# Connectors.net
KiCad netlist of a schematic drawn in Altium Designer
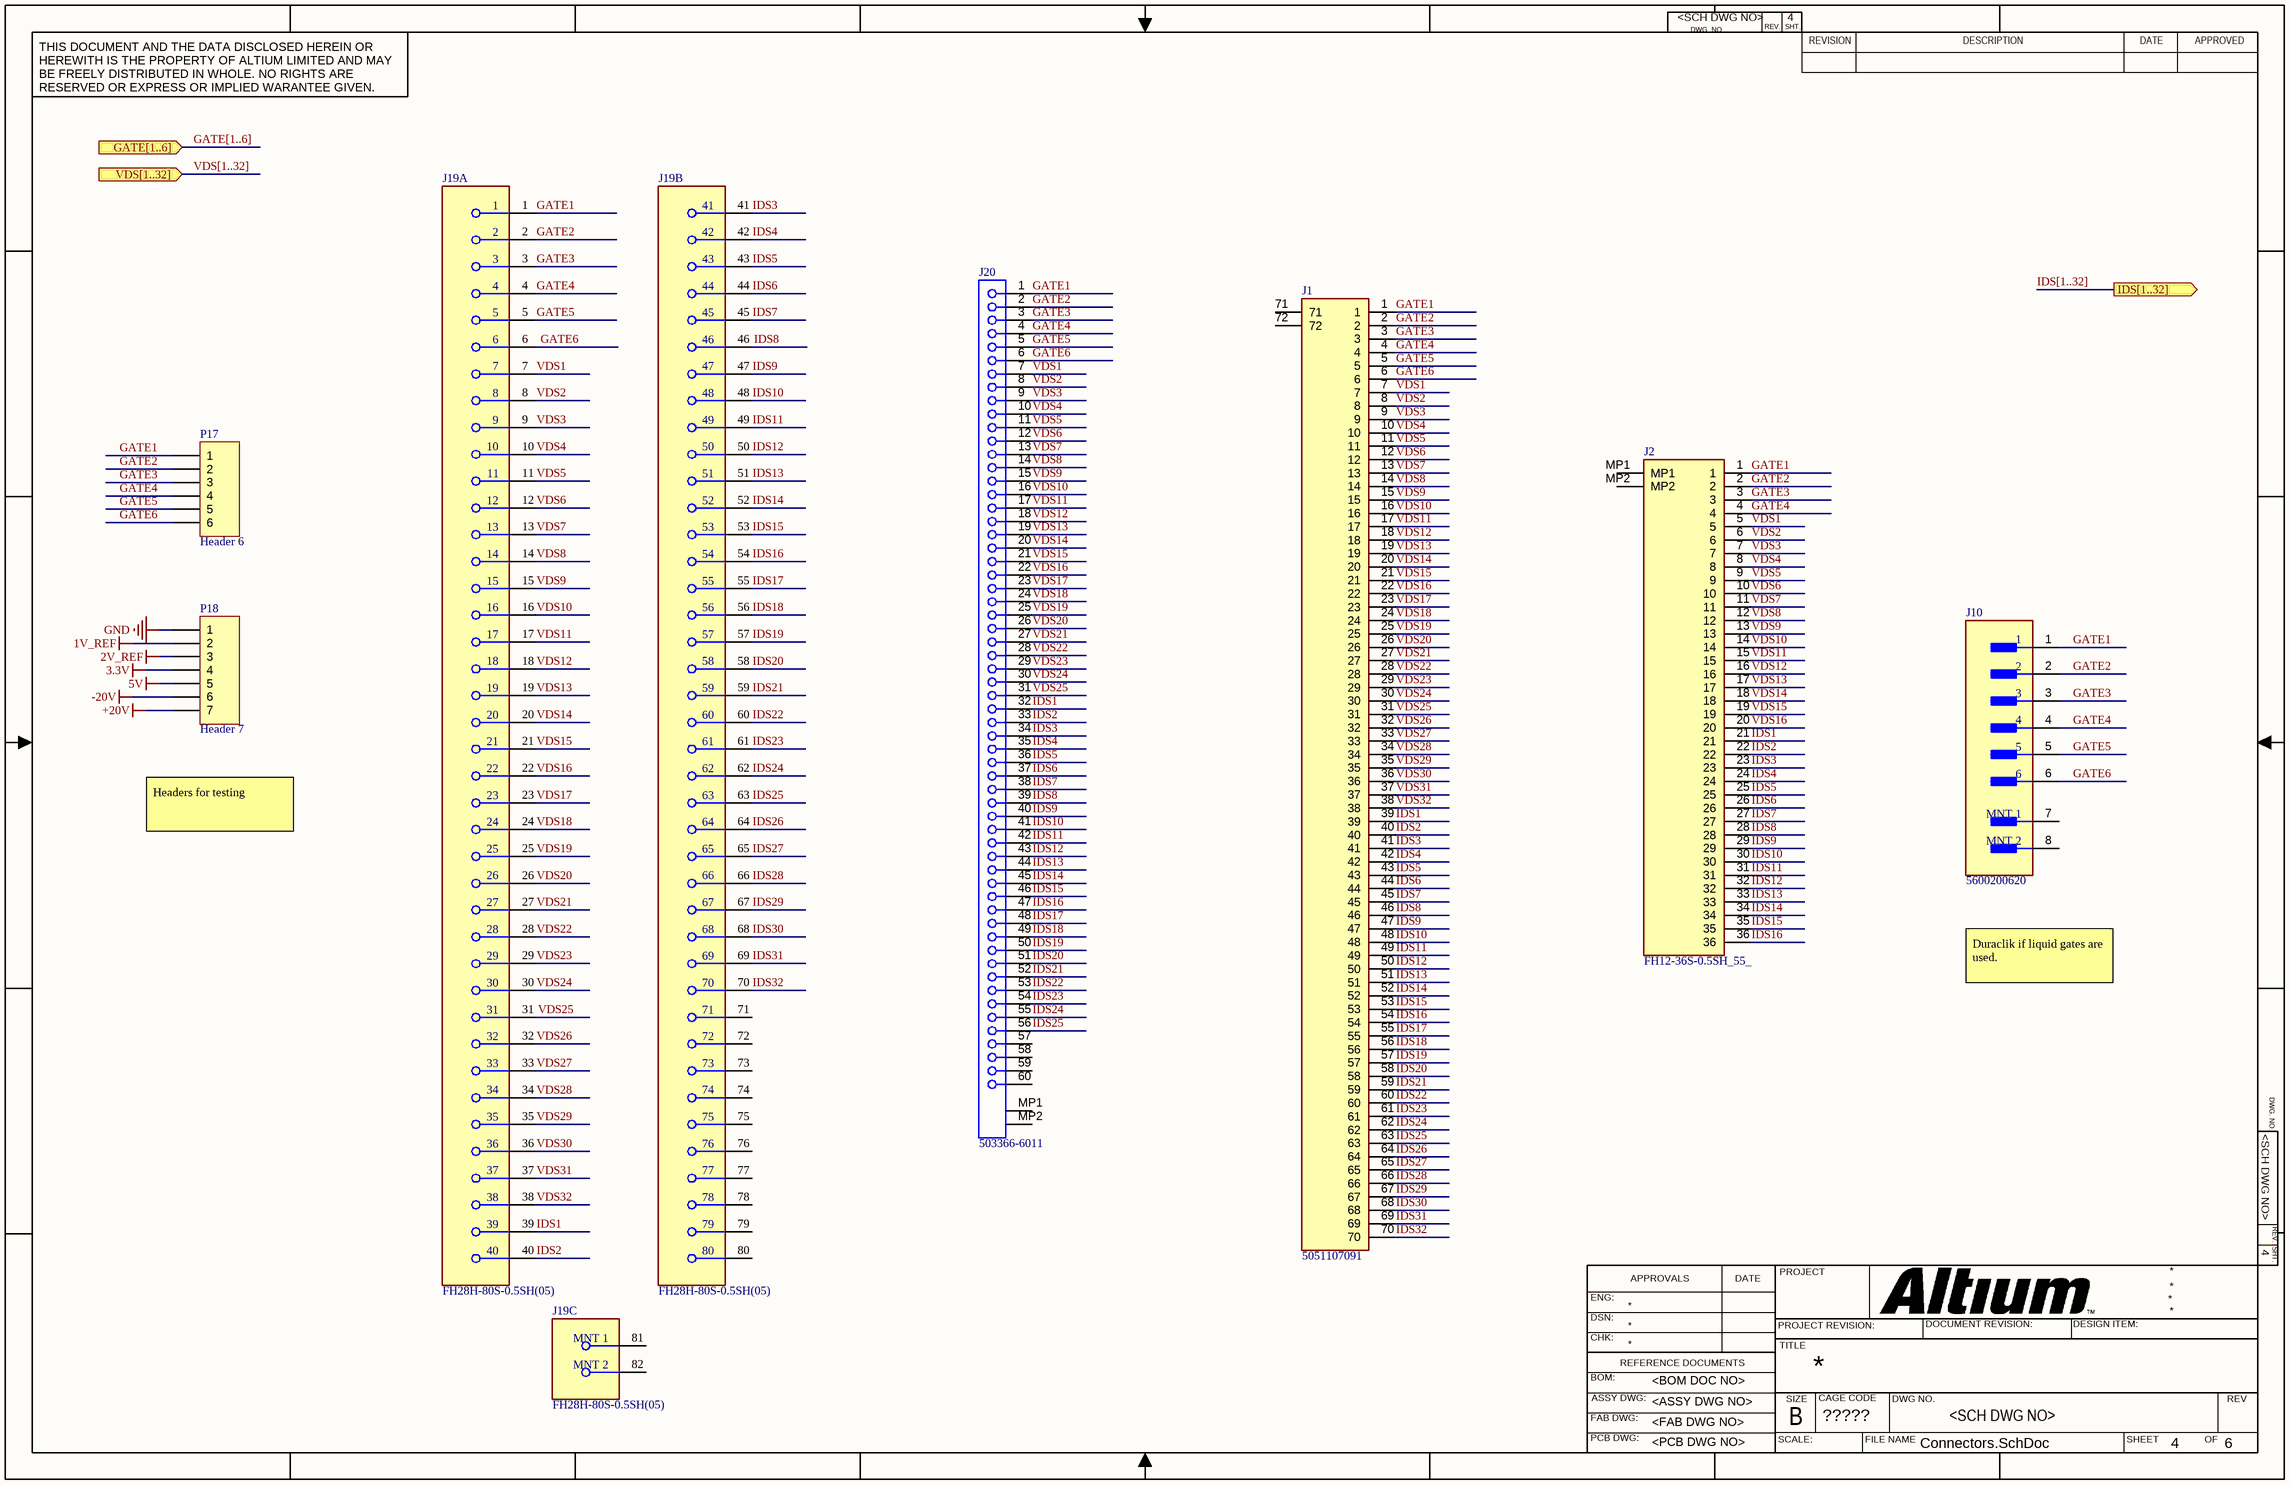
[diagram p0: Connectors.SchDoc]

(export (version "E")
  (design (tool "Eeschema 10.0.6"))
  (components
    (comp (ref "J1")
      (value "5051107091")
      (footprint "5051107091")
      (description "Connector")
      (libsource (lib "SamacSys") (part "5051107091"))
    )
    (comp (ref "J2")
      (value "FH12-36S-0.5SH_55_")
      (footprint "FH1236S05SH55")
      (description "Connector")
      (fields
        (field (name "MANUFACTURER_PART_NUMBER") "FH12-36S-0.5SH(55)")
        (field (name "MOUSER PART NUMBER") "798-FH12-36S-0.5SH55")
      )
      (libsource (lib "SamacSys") (part "FH12-36S-0.5SH_55_"))
    )
    (comp (ref "J10")
      (value "5600200620")
      (footprint "FP-5600200620-MFG")
      (description "CONN HEADER SMD 6POS 2MM")
      (fields
        (field (name "OCTOPART") "https://octopart.com/5600200620-molex-51767481")
        (field (name "MANUFACTURER") "Molex")
      )
      (libsource (lib "Altium Content Vault") (part "ed24c53d9ba001d1a2a686240a95171"))
    )
    (comp (ref "J19")
      (value "FH28H-80S-0.5SH(05)")
      (footprint "FP-FH28H-80S-0_5SH_05-MFG")
      (description "CONN FFC BOTTOM 80POS 0.50MM R/A")
      (libsource (lib "Altium Content Vault") (part "08075b3669470a400ec152efcfe4938"))
    )
    (comp (ref "J20")
      (value "503366-6011")
      (footprint "MOLX-503366-6011")
      (fields (field (name "MANUFACTURER") "Molex"))
      (libsource (lib "Altium Content Vault") (part "MOLX-503366-6011"))
    )
    (comp (ref "P17")
      (value "Header 6")
      (footprint "HDR1X6")
      (description "Header, 6-Pin")
      (fields (field (name "PUBLISHER") "Altium Limited"))
      (libsource (lib "Miscellaneous Connectors") (part "Header 6"))
    )
    (comp (ref "P18")
      (value "Header 7")
      (footprint "HDR1X7")
      (description "Header, 7-Pin")
      (fields (field (name "PUBLISHER") "Altium Limited"))
      (libsource (lib "Miscellaneous Connectors") (part "Header 7"))
    )
  )
  (nets
    (net (code "1") (name "+20V") (class "Default")
      (node (ref "P18") (pin "7") (pinfunction "7_7") (pintype "passive"))
    )
    (net (code "2") (name "-20V") (class "Default")
      (node (ref "P18") (pin "6") (pinfunction "6_6") (pintype "passive"))
    )
    (net (code "3") (name "/GATE1") (class "Default")
      (node (ref "J1") (pin "1") (pinfunction "1_1") (pintype "passive"))
      (node (ref "J10") (pin "1") (pinfunction "1_1") (pintype "passive"))
      (node (ref "J19") (pin "1") (pinfunction "1_1") (pintype "passive"))
      (node (ref "J2") (pin "1") (pinfunction "1_1") (pintype "passive"))
      (node (ref "J20") (pin "1") (pinfunction "1_1") (pintype "passive"))
      (node (ref "P17") (pin "1") (pinfunction "1_1") (pintype "passive"))
    )
    (net (code "4") (name "/GATE2") (class "Default")
      (node (ref "J1") (pin "2") (pinfunction "2_2") (pintype "passive"))
      (node (ref "J10") (pin "2") (pinfunction "2_2") (pintype "passive"))
      (node (ref "J19") (pin "2") (pinfunction "2_2") (pintype "passive"))
      (node (ref "J2") (pin "2") (pinfunction "2_2") (pintype "passive"))
      (node (ref "J20") (pin "2") (pinfunction "2_2") (pintype "passive"))
      (node (ref "P17") (pin "2") (pinfunction "2_2") (pintype "passive"))
    )
    (net (code "5") (name "/GATE3") (class "Default")
      (node (ref "J1") (pin "3") (pinfunction "3_3") (pintype "passive"))
      (node (ref "J10") (pin "3") (pinfunction "3_3") (pintype "passive"))
      (node (ref "J19") (pin "3") (pinfunction "3_3") (pintype "passive"))
      (node (ref "J2") (pin "3") (pinfunction "3_3") (pintype "passive"))
      (node (ref "J20") (pin "3") (pinfunction "3_3") (pintype "passive"))
      (node (ref "P17") (pin "3") (pinfunction "3_3") (pintype "passive"))
    )
    (net (code "6") (name "/GATE4") (class "Default")
      (node (ref "J1") (pin "4") (pinfunction "4_4") (pintype "passive"))
      (node (ref "J10") (pin "4") (pinfunction "4_4") (pintype "passive"))
      (node (ref "J19") (pin "4") (pinfunction "4_4") (pintype "passive"))
      (node (ref "J2") (pin "4") (pinfunction "4_4") (pintype "passive"))
      (node (ref "J20") (pin "4") (pinfunction "4_4") (pintype "passive"))
      (node (ref "P17") (pin "4") (pinfunction "4_4") (pintype "passive"))
    )
    (net (code "7") (name "/GATE5") (class "Default")
      (node (ref "J1") (pin "5") (pinfunction "5_5") (pintype "passive"))
      (node (ref "J10") (pin "5") (pinfunction "5_5") (pintype "passive"))
      (node (ref "J19") (pin "5") (pinfunction "5_5") (pintype "passive"))
      (node (ref "J20") (pin "5") (pinfunction "5_5") (pintype "passive"))
      (node (ref "P17") (pin "5") (pinfunction "5_5") (pintype "passive"))
    )
    (net (code "8") (name "/GATE6") (class "Default")
      (node (ref "J1") (pin "6") (pinfunction "6_6") (pintype "passive"))
      (node (ref "J10") (pin "6") (pinfunction "6_6") (pintype "passive"))
      (node (ref "J19") (pin "6") (pinfunction "6_6") (pintype "passive"))
      (node (ref "J20") (pin "6") (pinfunction "6_6") (pintype "passive"))
      (node (ref "P17") (pin "6") (pinfunction "6_6") (pintype "passive"))
    )
    (net (code "10") (name "/IDS1") (class "Default")
      (node (ref "J1") (pin "39") (pinfunction "39_39") (pintype "passive"))
      (node (ref "J19") (pin "39") (pinfunction "39_39") (pintype "passive"))
      (node (ref "J2") (pin "21") (pinfunction "21_21") (pintype "passive"))
      (node (ref "J20") (pin "32") (pinfunction "32_32") (pintype "passive"))
    )
    (net (code "11") (name "/IDS2") (class "Default")
      (node (ref "J1") (pin "40") (pinfunction "40_40") (pintype "passive"))
      (node (ref "J19") (pin "40") (pinfunction "40_40") (pintype "passive"))
      (node (ref "J2") (pin "22") (pinfunction "22_22") (pintype "passive"))
      (node (ref "J20") (pin "33") (pinfunction "33_33") (pintype "passive"))
    )
    (net (code "12") (name "/IDS3") (class "Default")
      (node (ref "J1") (pin "41") (pinfunction "41_41") (pintype "passive"))
      (node (ref "J19") (pin "41") (pinfunction "41_41") (pintype "passive"))
      (node (ref "J2") (pin "23") (pinfunction "23_23") (pintype "passive"))
      (node (ref "J20") (pin "34") (pinfunction "34_34") (pintype "passive"))
    )
    (net (code "13") (name "/IDS4") (class "Default")
      (node (ref "J1") (pin "42") (pinfunction "42_42") (pintype "passive"))
      (node (ref "J19") (pin "42") (pinfunction "42_42") (pintype "passive"))
      (node (ref "J2") (pin "24") (pinfunction "24_24") (pintype "passive"))
      (node (ref "J20") (pin "35") (pinfunction "35_35") (pintype "passive"))
    )
    (net (code "14") (name "/IDS5") (class "Default")
      (node (ref "J1") (pin "43") (pinfunction "43_43") (pintype "passive"))
      (node (ref "J19") (pin "43") (pinfunction "43_43") (pintype "passive"))
      (node (ref "J2") (pin "25") (pinfunction "25_25") (pintype "passive"))
      (node (ref "J20") (pin "36") (pinfunction "36_36") (pintype "passive"))
    )
    (net (code "15") (name "/IDS6") (class "Default")
      (node (ref "J1") (pin "44") (pinfunction "44_44") (pintype "passive"))
      (node (ref "J19") (pin "44") (pinfunction "44_44") (pintype "passive"))
      (node (ref "J2") (pin "26") (pinfunction "26_26") (pintype "passive"))
      (node (ref "J20") (pin "37") (pinfunction "37_37") (pintype "passive"))
    )
    (net (code "16") (name "/IDS7") (class "Default")
      (node (ref "J1") (pin "45") (pinfunction "45_45") (pintype "passive"))
      (node (ref "J19") (pin "45") (pinfunction "45_45") (pintype "passive"))
      (node (ref "J2") (pin "27") (pinfunction "27_27") (pintype "passive"))
      (node (ref "J20") (pin "38") (pinfunction "38_38") (pintype "passive"))
    )
    (net (code "17") (name "/IDS8") (class "Default")
      (node (ref "J1") (pin "46") (pinfunction "46_46") (pintype "passive"))
      (node (ref "J19") (pin "46") (pinfunction "46_46") (pintype "passive"))
      (node (ref "J2") (pin "28") (pinfunction "28_28") (pintype "passive"))
      (node (ref "J20") (pin "39") (pinfunction "39_39") (pintype "passive"))
    )
    (net (code "18") (name "/IDS9") (class "Default")
      (node (ref "J1") (pin "47") (pinfunction "47_47") (pintype "passive"))
      (node (ref "J19") (pin "47") (pinfunction "47_47") (pintype "passive"))
      (node (ref "J2") (pin "29") (pinfunction "29_29") (pintype "passive"))
      (node (ref "J20") (pin "40") (pinfunction "40_40") (pintype "passive"))
    )
    (net (code "19") (name "/IDS10") (class "Default")
      (node (ref "J1") (pin "48") (pinfunction "48_48") (pintype "passive"))
      (node (ref "J19") (pin "48") (pinfunction "48_48") (pintype "passive"))
      (node (ref "J2") (pin "30") (pinfunction "30_30") (pintype "passive"))
      (node (ref "J20") (pin "41") (pinfunction "41_41") (pintype "passive"))
    )
    (net (code "20") (name "/IDS11") (class "Default")
      (node (ref "J1") (pin "49") (pinfunction "49_49") (pintype "passive"))
      (node (ref "J19") (pin "49") (pinfunction "49_49") (pintype "passive"))
      (node (ref "J2") (pin "31") (pinfunction "31_31") (pintype "passive"))
      (node (ref "J20") (pin "42") (pinfunction "42_42") (pintype "passive"))
    )
    (net (code "21") (name "/IDS12") (class "Default")
      (node (ref "J1") (pin "50") (pinfunction "50_50") (pintype "passive"))
      (node (ref "J19") (pin "50") (pinfunction "50_50") (pintype "passive"))
      (node (ref "J2") (pin "32") (pinfunction "32_32") (pintype "passive"))
      (node (ref "J20") (pin "43") (pinfunction "43_43") (pintype "passive"))
    )
    (net (code "22") (name "/IDS13") (class "Default")
      (node (ref "J1") (pin "51") (pinfunction "51_51") (pintype "passive"))
      (node (ref "J19") (pin "51") (pinfunction "51_51") (pintype "passive"))
      (node (ref "J2") (pin "33") (pinfunction "33_33") (pintype "passive"))
      (node (ref "J20") (pin "44") (pinfunction "44_44") (pintype "passive"))
    )
    (net (code "23") (name "/IDS14") (class "Default")
      (node (ref "J1") (pin "52") (pinfunction "52_52") (pintype "passive"))
      (node (ref "J19") (pin "52") (pinfunction "52_52") (pintype "passive"))
      (node (ref "J2") (pin "34") (pinfunction "34_34") (pintype "passive"))
      (node (ref "J20") (pin "45") (pinfunction "45_45") (pintype "passive"))
    )
    (net (code "24") (name "/IDS15") (class "Default")
      (node (ref "J1") (pin "53") (pinfunction "53_53") (pintype "passive"))
      (node (ref "J19") (pin "53") (pinfunction "53_53") (pintype "passive"))
      (node (ref "J2") (pin "35") (pinfunction "35_35") (pintype "passive"))
      (node (ref "J20") (pin "46") (pinfunction "46_46") (pintype "passive"))
    )
    (net (code "25") (name "/IDS16") (class "Default")
      (node (ref "J1") (pin "54") (pinfunction "54_54") (pintype "passive"))
      (node (ref "J19") (pin "54") (pinfunction "54_54") (pintype "passive"))
      (node (ref "J2") (pin "36") (pinfunction "36_36") (pintype "passive"))
      (node (ref "J20") (pin "47") (pinfunction "47_47") (pintype "passive"))
    )
    (net (code "26") (name "/IDS17") (class "Default")
      (node (ref "J1") (pin "55") (pinfunction "55_55") (pintype "passive"))
      (node (ref "J19") (pin "55") (pinfunction "55_55") (pintype "passive"))
      (node (ref "J20") (pin "48") (pinfunction "48_48") (pintype "passive"))
    )
    (net (code "27") (name "/IDS18") (class "Default")
      (node (ref "J1") (pin "56") (pinfunction "56_56") (pintype "passive"))
      (node (ref "J19") (pin "56") (pinfunction "56_56") (pintype "passive"))
      (node (ref "J20") (pin "49") (pinfunction "49_49") (pintype "passive"))
    )
    (net (code "28") (name "/IDS19") (class "Default")
      (node (ref "J1") (pin "57") (pinfunction "57_57") (pintype "passive"))
      (node (ref "J19") (pin "57") (pinfunction "57_57") (pintype "passive"))
      (node (ref "J20") (pin "50") (pinfunction "50_50") (pintype "passive"))
    )
    (net (code "29") (name "/IDS20") (class "Default")
      (node (ref "J1") (pin "58") (pinfunction "58_58") (pintype "passive"))
      (node (ref "J19") (pin "58") (pinfunction "58_58") (pintype "passive"))
      (node (ref "J20") (pin "51") (pinfunction "51_51") (pintype "passive"))
    )
    (net (code "30") (name "/IDS21") (class "Default")
      (node (ref "J1") (pin "59") (pinfunction "59_59") (pintype "passive"))
      (node (ref "J19") (pin "59") (pinfunction "59_59") (pintype "passive"))
      (node (ref "J20") (pin "52") (pinfunction "52_52") (pintype "passive"))
    )
    (net (code "31") (name "/IDS22") (class "Default")
      (node (ref "J1") (pin "60") (pinfunction "60_60") (pintype "passive"))
      (node (ref "J19") (pin "60") (pinfunction "60_60") (pintype "passive"))
      (node (ref "J20") (pin "53") (pinfunction "53_53") (pintype "passive"))
    )
    (net (code "32") (name "/IDS23") (class "Default")
      (node (ref "J1") (pin "61") (pinfunction "61_61") (pintype "passive"))
      (node (ref "J19") (pin "61") (pinfunction "61_61") (pintype "passive"))
      (node (ref "J20") (pin "54") (pinfunction "54_54") (pintype "passive"))
    )
    (net (code "33") (name "/IDS24") (class "Default")
      (node (ref "J1") (pin "62") (pinfunction "62_62") (pintype "passive"))
      (node (ref "J19") (pin "62") (pinfunction "62_62") (pintype "passive"))
      (node (ref "J20") (pin "55") (pinfunction "55_55") (pintype "passive"))
    )
    (net (code "34") (name "/IDS25") (class "Default")
      (node (ref "J1") (pin "63") (pinfunction "63_63") (pintype "passive"))
      (node (ref "J19") (pin "63") (pinfunction "63_63") (pintype "passive"))
      (node (ref "J20") (pin "56") (pinfunction "56_56") (pintype "passive"))
    )
    (net (code "35") (name "/IDS26") (class "Default")
      (node (ref "J1") (pin "64") (pinfunction "64_64") (pintype "passive"))
      (node (ref "J19") (pin "64") (pinfunction "64_64") (pintype "passive"))
    )
    (net (code "36") (name "/IDS27") (class "Default")
      (node (ref "J1") (pin "65") (pinfunction "65_65") (pintype "passive"))
      (node (ref "J19") (pin "65") (pinfunction "65_65") (pintype "passive"))
    )
    (net (code "37") (name "/IDS28") (class "Default")
      (node (ref "J1") (pin "66") (pinfunction "66_66") (pintype "passive"))
      (node (ref "J19") (pin "66") (pinfunction "66_66") (pintype "passive"))
    )
    (net (code "38") (name "/IDS29") (class "Default")
      (node (ref "J1") (pin "67") (pinfunction "67_67") (pintype "passive"))
      (node (ref "J19") (pin "67") (pinfunction "67_67") (pintype "passive"))
    )
    (net (code "39") (name "/IDS30") (class "Default")
      (node (ref "J1") (pin "68") (pinfunction "68_68") (pintype "passive"))
      (node (ref "J19") (pin "68") (pinfunction "68_68") (pintype "passive"))
    )
    (net (code "40") (name "/IDS31") (class "Default")
      (node (ref "J1") (pin "69") (pinfunction "69_69") (pintype "passive"))
      (node (ref "J19") (pin "69") (pinfunction "69_69") (pintype "passive"))
    )
    (net (code "41") (name "/IDS32") (class "Default")
      (node (ref "J1") (pin "70") (pinfunction "70_70") (pintype "passive"))
      (node (ref "J19") (pin "70") (pinfunction "70_70") (pintype "passive"))
    )
    (net (code "43") (name "/VDS1") (class "Default")
      (node (ref "J1") (pin "7") (pinfunction "7_7") (pintype "passive"))
      (node (ref "J19") (pin "7") (pinfunction "7_7") (pintype "passive"))
      (node (ref "J2") (pin "5") (pinfunction "5_5") (pintype "passive"))
      (node (ref "J20") (pin "7") (pinfunction "7_7") (pintype "passive"))
    )
    (net (code "44") (name "/VDS2") (class "Default")
      (node (ref "J1") (pin "8") (pinfunction "8_8") (pintype "passive"))
      (node (ref "J19") (pin "8") (pinfunction "8_8") (pintype "passive"))
      (node (ref "J2") (pin "6") (pinfunction "6_6") (pintype "passive"))
      (node (ref "J20") (pin "8") (pinfunction "8_8") (pintype "passive"))
    )
    (net (code "45") (name "/VDS3") (class "Default")
      (node (ref "J1") (pin "9") (pinfunction "9_9") (pintype "passive"))
      (node (ref "J19") (pin "9") (pinfunction "9_9") (pintype "passive"))
      (node (ref "J2") (pin "7") (pinfunction "7_7") (pintype "passive"))
      (node (ref "J20") (pin "9") (pinfunction "9_9") (pintype "passive"))
    )
    (net (code "46") (name "/VDS4") (class "Default")
      (node (ref "J1") (pin "10") (pinfunction "10_10") (pintype "passive"))
      (node (ref "J19") (pin "10") (pinfunction "10_10") (pintype "passive"))
      (node (ref "J2") (pin "8") (pinfunction "8_8") (pintype "passive"))
      (node (ref "J20") (pin "10") (pinfunction "10_10") (pintype "passive"))
    )
    (net (code "47") (name "/VDS5") (class "Default")
      (node (ref "J1") (pin "11") (pinfunction "11_11") (pintype "passive"))
      (node (ref "J19") (pin "11") (pinfunction "11_11") (pintype "passive"))
      (node (ref "J2") (pin "9") (pinfunction "9_9") (pintype "passive"))
      (node (ref "J20") (pin "11") (pinfunction "11_11") (pintype "passive"))
    )
    (net (code "48") (name "/VDS6") (class "Default")
      (node (ref "J1") (pin "12") (pinfunction "12_12") (pintype "passive"))
      (node (ref "J19") (pin "12") (pinfunction "12_12") (pintype "passive"))
      (node (ref "J2") (pin "10") (pinfunction "10_10") (pintype "passive"))
      (node (ref "J20") (pin "12") (pinfunction "12_12") (pintype "passive"))
    )
    (net (code "49") (name "/VDS7") (class "Default")
      (node (ref "J1") (pin "13") (pinfunction "13_13") (pintype "passive"))
      (node (ref "J19") (pin "13") (pinfunction "13_13") (pintype "passive"))
      (node (ref "J2") (pin "11") (pinfunction "11_11") (pintype "passive"))
      (node (ref "J20") (pin "13") (pinfunction "13_13") (pintype "passive"))
    )
    (net (code "50") (name "/VDS8") (class "Default")
      (node (ref "J1") (pin "14") (pinfunction "14_14") (pintype "passive"))
      (node (ref "J19") (pin "14") (pinfunction "14_14") (pintype "passive"))
      (node (ref "J2") (pin "12") (pinfunction "12_12") (pintype "passive"))
      (node (ref "J20") (pin "14") (pinfunction "14_14") (pintype "passive"))
    )
    (net (code "51") (name "/VDS9") (class "Default")
      (node (ref "J1") (pin "15") (pinfunction "15_15") (pintype "passive"))
      (node (ref "J19") (pin "15") (pinfunction "15_15") (pintype "passive"))
      (node (ref "J2") (pin "13") (pinfunction "13_13") (pintype "passive"))
      (node (ref "J20") (pin "15") (pinfunction "15_15") (pintype "passive"))
    )
    (net (code "52") (name "/VDS10") (class "Default")
      (node (ref "J1") (pin "16") (pinfunction "16_16") (pintype "passive"))
      (node (ref "J19") (pin "16") (pinfunction "16_16") (pintype "passive"))
      (node (ref "J2") (pin "14") (pinfunction "14_14") (pintype "passive"))
      (node (ref "J20") (pin "16") (pinfunction "16_16") (pintype "passive"))
    )
    (net (code "53") (name "/VDS11") (class "Default")
      (node (ref "J1") (pin "17") (pinfunction "17_17") (pintype "passive"))
      (node (ref "J19") (pin "17") (pinfunction "17_17") (pintype "passive"))
      (node (ref "J2") (pin "15") (pinfunction "15_15") (pintype "passive"))
      (node (ref "J20") (pin "17") (pinfunction "17_17") (pintype "passive"))
    )
    (net (code "54") (name "/VDS12") (class "Default")
      (node (ref "J1") (pin "18") (pinfunction "18_18") (pintype "passive"))
      (node (ref "J19") (pin "18") (pinfunction "18_18") (pintype "passive"))
      (node (ref "J2") (pin "16") (pinfunction "16_16") (pintype "passive"))
      (node (ref "J20") (pin "18") (pinfunction "18_18") (pintype "passive"))
    )
    (net (code "55") (name "/VDS13") (class "Default")
      (node (ref "J1") (pin "19") (pinfunction "19_19") (pintype "passive"))
      (node (ref "J19") (pin "19") (pinfunction "19_19") (pintype "passive"))
      (node (ref "J2") (pin "17") (pinfunction "17_17") (pintype "passive"))
      (node (ref "J20") (pin "19") (pinfunction "19_19") (pintype "passive"))
    )
    (net (code "56") (name "/VDS14") (class "Default")
      (node (ref "J1") (pin "20") (pinfunction "20_20") (pintype "passive"))
      (node (ref "J19") (pin "20") (pinfunction "20_20") (pintype "passive"))
      (node (ref "J2") (pin "18") (pinfunction "18_18") (pintype "passive"))
      (node (ref "J20") (pin "20") (pinfunction "20_20") (pintype "passive"))
    )
    (net (code "57") (name "/VDS15") (class "Default")
      (node (ref "J1") (pin "21") (pinfunction "21_21") (pintype "passive"))
      (node (ref "J19") (pin "21") (pinfunction "21_21") (pintype "passive"))
      (node (ref "J2") (pin "19") (pinfunction "19_19") (pintype "passive"))
      (node (ref "J20") (pin "21") (pinfunction "21_21") (pintype "passive"))
    )
    (net (code "58") (name "/VDS16") (class "Default")
      (node (ref "J1") (pin "22") (pinfunction "22_22") (pintype "passive"))
      (node (ref "J19") (pin "22") (pinfunction "22_22") (pintype "passive"))
      (node (ref "J2") (pin "20") (pinfunction "20_20") (pintype "passive"))
      (node (ref "J20") (pin "22") (pinfunction "22_22") (pintype "passive"))
    )
    (net (code "59") (name "/VDS17") (class "Default")
      (node (ref "J1") (pin "23") (pinfunction "23_23") (pintype "passive"))
      (node (ref "J19") (pin "23") (pinfunction "23_23") (pintype "passive"))
      (node (ref "J20") (pin "23") (pinfunction "23_23") (pintype "passive"))
    )
    (net (code "60") (name "/VDS18") (class "Default")
      (node (ref "J1") (pin "24") (pinfunction "24_24") (pintype "passive"))
      (node (ref "J19") (pin "24") (pinfunction "24_24") (pintype "passive"))
      (node (ref "J20") (pin "24") (pinfunction "24_24") (pintype "passive"))
    )
    (net (code "61") (name "/VDS19") (class "Default")
      (node (ref "J1") (pin "25") (pinfunction "25_25") (pintype "passive"))
      (node (ref "J19") (pin "25") (pinfunction "25_25") (pintype "passive"))
      (node (ref "J20") (pin "25") (pinfunction "25_25") (pintype "passive"))
    )
    (net (code "62") (name "/VDS20") (class "Default")
      (node (ref "J1") (pin "26") (pinfunction "26_26") (pintype "passive"))
      (node (ref "J19") (pin "26") (pinfunction "26_26") (pintype "passive"))
      (node (ref "J20") (pin "26") (pinfunction "26_26") (pintype "passive"))
    )
    (net (code "63") (name "/VDS21") (class "Default")
      (node (ref "J1") (pin "27") (pinfunction "27_27") (pintype "passive"))
      (node (ref "J19") (pin "27") (pinfunction "27_27") (pintype "passive"))
      (node (ref "J20") (pin "27") (pinfunction "27_27") (pintype "passive"))
    )
    (net (code "64") (name "/VDS22") (class "Default")
      (node (ref "J1") (pin "28") (pinfunction "28_28") (pintype "passive"))
      (node (ref "J19") (pin "28") (pinfunction "28_28") (pintype "passive"))
      (node (ref "J20") (pin "28") (pinfunction "28_28") (pintype "passive"))
    )
    (net (code "65") (name "/VDS23") (class "Default")
      (node (ref "J1") (pin "29") (pinfunction "29_29") (pintype "passive"))
      (node (ref "J19") (pin "29") (pinfunction "29_29") (pintype "passive"))
      (node (ref "J20") (pin "29") (pinfunction "29_29") (pintype "passive"))
    )
    (net (code "66") (name "/VDS24") (class "Default")
      (node (ref "J1") (pin "30") (pinfunction "30_30") (pintype "passive"))
      (node (ref "J19") (pin "30") (pinfunction "30_30") (pintype "passive"))
      (node (ref "J20") (pin "30") (pinfunction "30_30") (pintype "passive"))
    )
    (net (code "67") (name "/VDS25") (class "Default")
      (node (ref "J1") (pin "31") (pinfunction "31_31") (pintype "passive"))
      (node (ref "J19") (pin "31") (pinfunction "31_31") (pintype "passive"))
      (node (ref "J20") (pin "31") (pinfunction "31_31") (pintype "passive"))
    )
    (net (code "68") (name "/VDS26") (class "Default")
      (node (ref "J1") (pin "32") (pinfunction "32_32") (pintype "passive"))
      (node (ref "J19") (pin "32") (pinfunction "32_32") (pintype "passive"))
    )
    (net (code "69") (name "/VDS27") (class "Default")
      (node (ref "J1") (pin "33") (pinfunction "33_33") (pintype "passive"))
      (node (ref "J19") (pin "33") (pinfunction "33_33") (pintype "passive"))
    )
    (net (code "70") (name "/VDS28") (class "Default")
      (node (ref "J1") (pin "34") (pinfunction "34_34") (pintype "passive"))
      (node (ref "J19") (pin "34") (pinfunction "34_34") (pintype "passive"))
    )
    (net (code "71") (name "/VDS29") (class "Default")
      (node (ref "J1") (pin "35") (pinfunction "35_35") (pintype "passive"))
      (node (ref "J19") (pin "35") (pinfunction "35_35") (pintype "passive"))
    )
    (net (code "72") (name "/VDS30") (class "Default")
      (node (ref "J1") (pin "36") (pinfunction "36_36") (pintype "passive"))
      (node (ref "J19") (pin "36") (pinfunction "36_36") (pintype "passive"))
    )
    (net (code "73") (name "/VDS31") (class "Default")
      (node (ref "J1") (pin "37") (pinfunction "37_37") (pintype "passive"))
      (node (ref "J19") (pin "37") (pinfunction "37_37") (pintype "passive"))
    )
    (net (code "74") (name "/VDS32") (class "Default")
      (node (ref "J1") (pin "38") (pinfunction "38_38") (pintype "passive"))
      (node (ref "J19") (pin "38") (pinfunction "38_38") (pintype "passive"))
    )
    (net (code "76") (name "1V_REF") (class "Default")
      (node (ref "P18") (pin "2") (pinfunction "2_2") (pintype "passive"))
    )
    (net (code "77") (name "2V_REF") (class "Default")
      (node (ref "P18") (pin "3") (pinfunction "3_3") (pintype "passive"))
    )
    (net (code "78") (name "3.3V") (class "Default")
      (node (ref "P18") (pin "4") (pinfunction "4_4") (pintype "passive"))
    )
    (net (code "79") (name "5V") (class "Default")
      (node (ref "P18") (pin "5") (pinfunction "5_5") (pintype "passive"))
    )
    (net (code "80") (name "GND") (class "Default")
      (node (ref "P18") (pin "1") (pinfunction "1_1") (pintype "passive"))
    )
    (net (code "81") (name "unconnected-(J1-Pad71)") (class "Default")
      (node (ref "J1") (pin "71") (pinfunction "71_71") (pintype "passive"))
    )
    (net (code "82") (name "unconnected-(J1-Pad72)") (class "Default")
      (node (ref "J1") (pin "72") (pinfunction "72_72") (pintype "passive"))
    )
    (net (code "83") (name "unconnected-(J2-PadMP1)") (class "Default")
      (node (ref "J2") (pin "MP1") (pinfunction "MP1_MP1") (pintype "passive"))
    )
    (net (code "84") (name "unconnected-(J2-PadMP2)") (class "Default")
      (node (ref "J2") (pin "MP2") (pinfunction "MP2_MP2") (pintype "passive"))
    )
    (net (code "85") (name "unconnected-(J10-MNT_1-Pad7)") (class "Default")
      (node (ref "J10") (pin "7") (pinfunction "MNT_1_7") (pintype "passive"))
    )
    (net (code "86") (name "unconnected-(J10-MNT_2-Pad8)") (class "Default")
      (node (ref "J10") (pin "8") (pinfunction "MNT_2_8") (pintype "passive"))
    )
    (net (code "87") (name "unconnected-(J19-Pad71)") (class "Default")
      (node (ref "J19") (pin "71") (pinfunction "71_71") (pintype "passive"))
    )
    (net (code "88") (name "unconnected-(J19-Pad72)") (class "Default")
      (node (ref "J19") (pin "72") (pinfunction "72_72") (pintype "passive"))
    )
    (net (code "89") (name "unconnected-(J19-Pad73)") (class "Default")
      (node (ref "J19") (pin "73") (pinfunction "73_73") (pintype "passive"))
    )
    (net (code "90") (name "unconnected-(J19-Pad74)") (class "Default")
      (node (ref "J19") (pin "74") (pinfunction "74_74") (pintype "passive"))
    )
    (net (code "91") (name "unconnected-(J19-Pad75)") (class "Default")
      (node (ref "J19") (pin "75") (pinfunction "75_75") (pintype "passive"))
    )
    (net (code "92") (name "unconnected-(J19-Pad76)") (class "Default")
      (node (ref "J19") (pin "76") (pinfunction "76_76") (pintype "passive"))
    )
    (net (code "93") (name "unconnected-(J19-Pad77)") (class "Default")
      (node (ref "J19") (pin "77") (pinfunction "77_77") (pintype "passive"))
    )
    (net (code "94") (name "unconnected-(J19-Pad78)") (class "Default")
      (node (ref "J19") (pin "78") (pinfunction "78_78") (pintype "passive"))
    )
    (net (code "95") (name "unconnected-(J19-Pad79)") (class "Default")
      (node (ref "J19") (pin "79") (pinfunction "79_79") (pintype "passive"))
    )
    (net (code "96") (name "unconnected-(J19-Pad80)") (class "Default")
      (node (ref "J19") (pin "80") (pinfunction "80_80") (pintype "passive"))
    )
    (net (code "97") (name "unconnected-(J19C-MNT_1-Pad81)") (class "Default")
      (node (ref "J19") (pin "81") (pinfunction "MNT_1_81") (pintype "passive"))
    )
    (net (code "98") (name "unconnected-(J19C-MNT_2-Pad82)") (class "Default")
      (node (ref "J19") (pin "82") (pinfunction "MNT_2_82") (pintype "passive"))
    )
    (net (code "99") (name "unconnected-(J20-Pad57)") (class "Default")
      (node (ref "J20") (pin "57") (pinfunction "57_57") (pintype "passive"))
    )
    (net (code "100") (name "unconnected-(J20-Pad58)") (class "Default")
      (node (ref "J20") (pin "58") (pinfunction "58_58") (pintype "passive"))
    )
    (net (code "101") (name "unconnected-(J20-Pad59)") (class "Default")
      (node (ref "J20") (pin "59") (pinfunction "59_59") (pintype "passive"))
    )
    (net (code "102") (name "unconnected-(J20-Pad60)") (class "Default")
      (node (ref "J20") (pin "60") (pinfunction "60_60") (pintype "passive"))
    )
    (net (code "103") (name "unconnected-(J20-PadMP1)") (class "Default")
      (node (ref "J20") (pin "MP1") (pinfunction "MP1_MP1") (pintype "passive"))
    )
    (net (code "104") (name "unconnected-(J20-PadMP2)") (class "Default")
      (node (ref "J20") (pin "MP2") (pinfunction "MP2_MP2") (pintype "passive"))
    )
  )
)
